# LEDBoard.net
KiCad netlist of a schematic drawn in Altium Designer
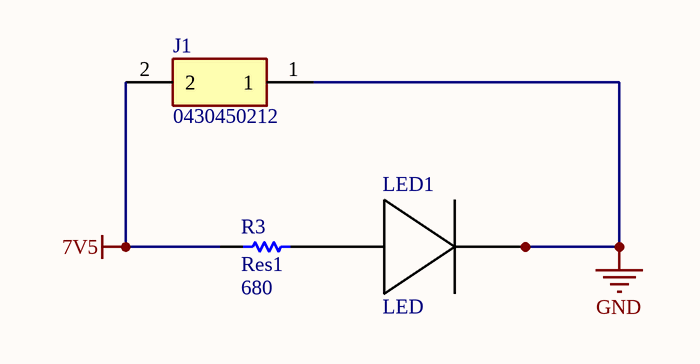
[diagram p0: LEDBoard.SchDoc]

(export (version "E")
  (design (tool "Eeschema 10.0.6"))
  (components
    (comp (ref "J1")
      (value "0430450212")
      (footprint "SamacSys:0430450212")
      (description "Connector")
      (libsource (lib "SamacSys") (part "0430450212"))
    )
    (comp (ref "LED1")
      (value "LED")
      (footprint "L944-UV265-2-20")
      (libsource (lib "L944-UV265-2-20") (part "LED"))
    )
    (comp (ref "R3")
      (value "Res1")
      (footprint "6-0805_M")
      (description "Resistor")
      (fields (field (name "ALTIUM_VALUE") "680") (field (name "PUBLISHER") "Altium Limited"))
      (libsource (lib "Miscellaneous Devices") (part "Res1"))
    )
  )
  (nets
    (net (code "1") (name "7V5") (class "Default")
      (node (ref "J1") (pin "2") (pinfunction "2_2") (pintype "passive"))
      (node (ref "R3") (pin "1") (pinfunction "1_1") (pintype "passive"))
    )
    (net (code "2") (name "GND") (class "Default")
      (node (ref "J1") (pin "1") (pinfunction "1_1") (pintype "passive"))
      (node (ref "LED1") (pin "1") (pinfunction "1_1") (pintype "passive"))
      (node (ref "LED1") (pin "3") (pinfunction "3_3") (pintype "passive"))
    )
    (net (code "3") (name "Net-(LED1-Pad2)") (class "Default")
      (node (ref "LED1") (pin "2") (pinfunction "2_2") (pintype "passive"))
      (node (ref "R3") (pin "2") (pinfunction "2_2") (pintype "passive"))
    )
  )
)
